# uMultimeter_EXP_Sch.net
KiCad netlist of a schematic drawn in Altium Designer
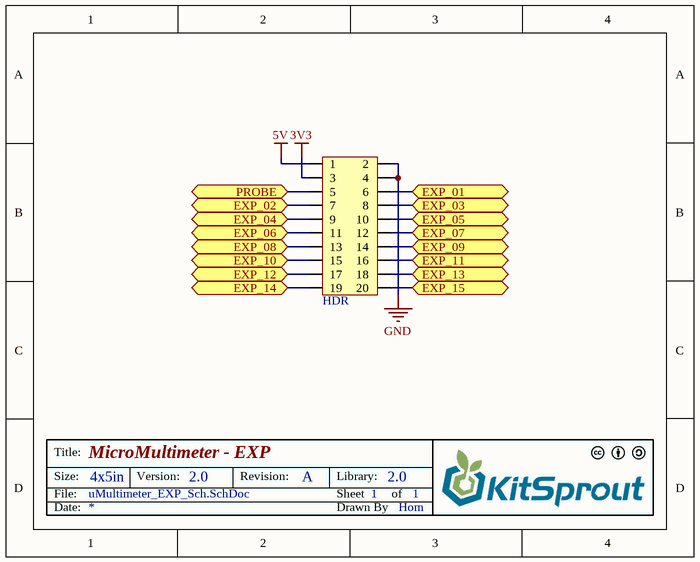
[diagram p0: uMultimeter_EXP_Sch.SchDoc]

(export (version "E")
  (design (tool "Eeschema 10.0.6"))
  (components
    (comp (ref "HDR")
      (value "HDR2x10_2.54")
      (footprint "PCB_ConnectorHDR:HDR2X10_2.54_180H")
      (description "Header")
      (libsource (lib "SCH_ConnectorHDR") (part "HDR2x10_2.54"))
    )
  )
  (nets
    (net (code "1") (name "/EXP_01") (class "Default")
      (node (ref "HDR") (pin "6") (pinfunction "6_6") (pintype "passive"))
    )
    (net (code "2") (name "/EXP_02") (class "Default")
      (node (ref "HDR") (pin "7") (pinfunction "7_7") (pintype "passive"))
    )
    (net (code "3") (name "/EXP_03") (class "Default")
      (node (ref "HDR") (pin "8") (pinfunction "8_8") (pintype "passive"))
    )
    (net (code "4") (name "/EXP_04") (class "Default")
      (node (ref "HDR") (pin "9") (pinfunction "9_9") (pintype "passive"))
    )
    (net (code "5") (name "/EXP_05") (class "Default")
      (node (ref "HDR") (pin "10") (pinfunction "10_10") (pintype "passive"))
    )
    (net (code "6") (name "/EXP_06") (class "Default")
      (node (ref "HDR") (pin "11") (pinfunction "11_11") (pintype "passive"))
    )
    (net (code "7") (name "/EXP_07") (class "Default")
      (node (ref "HDR") (pin "12") (pinfunction "12_12") (pintype "passive"))
    )
    (net (code "8") (name "/EXP_08") (class "Default")
      (node (ref "HDR") (pin "13") (pinfunction "13_13") (pintype "passive"))
    )
    (net (code "9") (name "/EXP_09") (class "Default")
      (node (ref "HDR") (pin "14") (pinfunction "14_14") (pintype "passive"))
    )
    (net (code "10") (name "/EXP_10") (class "Default")
      (node (ref "HDR") (pin "15") (pinfunction "15_15") (pintype "passive"))
    )
    (net (code "11") (name "/EXP_11") (class "Default")
      (node (ref "HDR") (pin "16") (pinfunction "16_16") (pintype "passive"))
    )
    (net (code "12") (name "/EXP_12") (class "Default")
      (node (ref "HDR") (pin "17") (pinfunction "17_17") (pintype "passive"))
    )
    (net (code "13") (name "/EXP_13") (class "Default")
      (node (ref "HDR") (pin "18") (pinfunction "18_18") (pintype "passive"))
    )
    (net (code "14") (name "/EXP_14") (class "Default")
      (node (ref "HDR") (pin "19") (pinfunction "19_19") (pintype "passive"))
    )
    (net (code "15") (name "/EXP_15") (class "Default")
      (node (ref "HDR") (pin "20") (pinfunction "20_20") (pintype "passive"))
    )
    (net (code "16") (name "/PROBE") (class "Default")
      (node (ref "HDR") (pin "5") (pinfunction "5_5") (pintype "passive"))
    )
    (net (code "17") (name "3V3") (class "Default")
      (node (ref "HDR") (pin "3") (pinfunction "3_3") (pintype "passive"))
    )
    (net (code "18") (name "5V") (class "Default")
      (node (ref "HDR") (pin "1") (pinfunction "1_1") (pintype "passive"))
    )
    (net (code "19") (name "GND") (class "Default")
      (node (ref "HDR") (pin "2") (pinfunction "2_2") (pintype "passive"))
      (node (ref "HDR") (pin "4") (pinfunction "4_4") (pintype "passive"))
    )
  )
)
